# FPGA_GPIO.net
KiCad netlist of a schematic drawn in Altium Designer
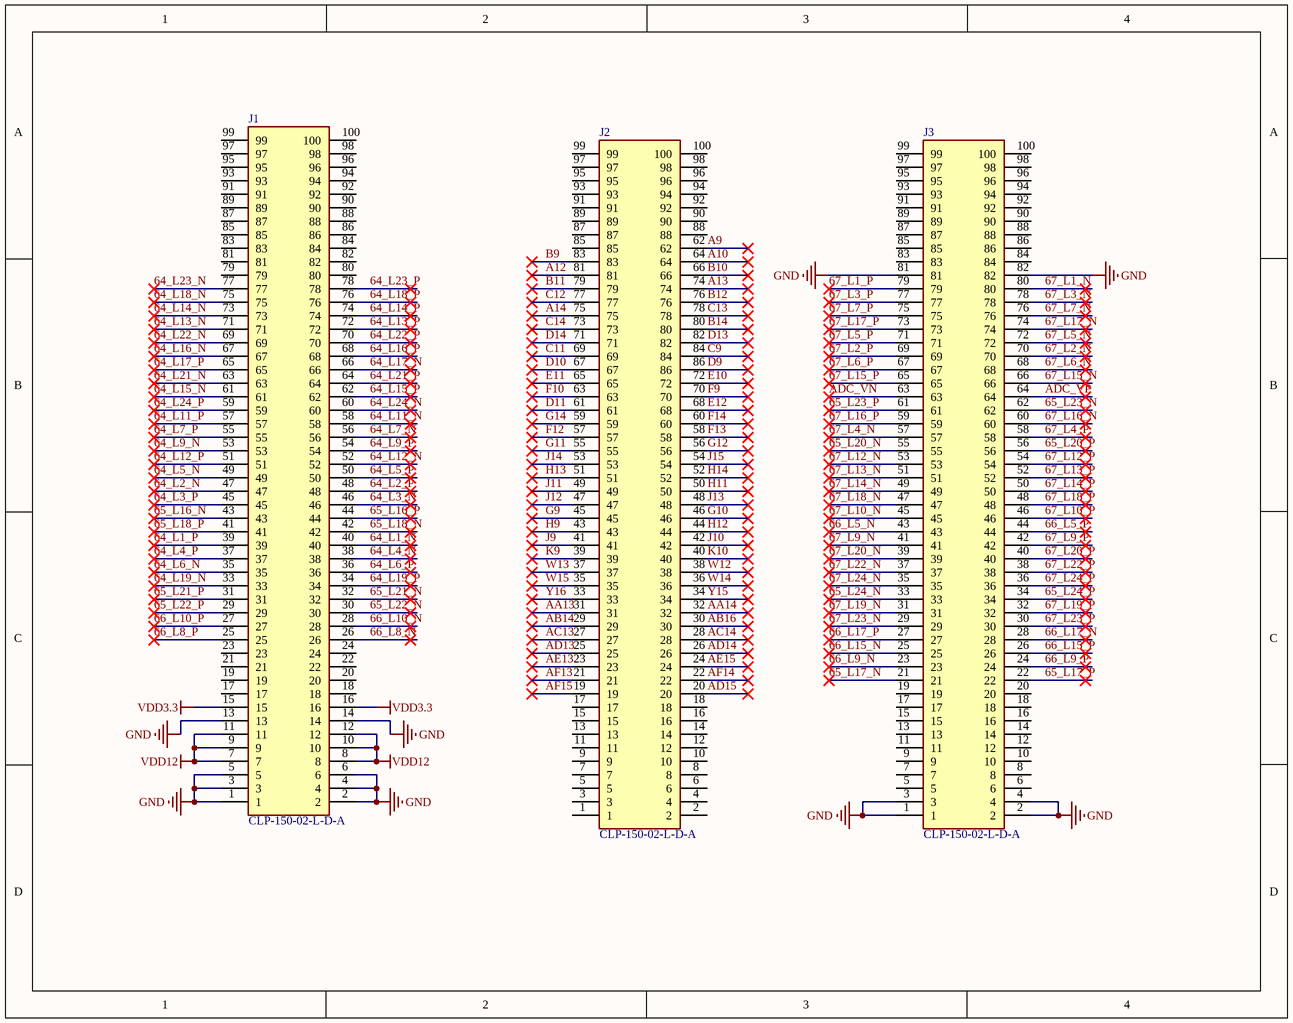
[diagram p0: FPGA_GPIO.SchDoc]

(export (version "E")
  (design (tool "Eeschema 10.0.6"))
  (components
    (comp (ref "J1")
      (value "CLP-150-02-L-D-A")
      (footprint "SamacSys:CLP-150-02-XXX-D-A")
      (description "Connector")
      (libsource (lib "") (part "CLP-150-02-L-D-A_1"))
    )
    (comp (ref "J2")
      (value "CLP-150-02-L-D-A")
      (footprint "SamacSys:CLP-150-02-XXX-D-A")
      (description "Connector")
      (libsource (lib "SamacSys") (part "CLP-150-02-L-D-A"))
    )
    (comp (ref "J3")
      (value "CLP-150-02-L-D-A")
      (footprint "SamacSys:CLP-150-02-XXX-D-A")
      (description "Connector")
      (libsource (lib "") (part "CLP-150-02-L-D-A_1"))
    )
  )
  (nets
    (net (code "1") (name "/64_L1_N") (class "Default")
      (node (ref "J1") (pin "40") (pinfunction "40_40") (pintype "passive"))
    )
    (net (code "2") (name "/64_L1_P") (class "Default")
      (node (ref "J1") (pin "39") (pinfunction "39_39") (pintype "passive+no_connect"))
    )
    (net (code "3") (name "/64_L2_N") (class "Default")
      (node (ref "J1") (pin "47") (pinfunction "47_47") (pintype "passive+no_connect"))
    )
    (net (code "4") (name "/64_L2_P") (class "Default")
      (node (ref "J1") (pin "48") (pinfunction "48_48") (pintype "passive"))
    )
    (net (code "5") (name "/64_L3_N") (class "Default")
      (node (ref "J1") (pin "46") (pinfunction "46_46") (pintype "passive"))
    )
    (net (code "6") (name "/64_L3_P") (class "Default")
      (node (ref "J1") (pin "45") (pinfunction "45_45") (pintype "passive+no_connect"))
    )
    (net (code "7") (name "/64_L4_N") (class "Default")
      (node (ref "J1") (pin "38") (pinfunction "38_38") (pintype "passive"))
    )
    (net (code "8") (name "/64_L4_P") (class "Default")
      (node (ref "J1") (pin "37") (pinfunction "37_37") (pintype "passive+no_connect"))
    )
    (net (code "9") (name "/64_L5_N") (class "Default")
      (node (ref "J1") (pin "49") (pinfunction "49_49") (pintype "passive+no_connect"))
    )
    (net (code "10") (name "/64_L5_P") (class "Default")
      (node (ref "J1") (pin "50") (pinfunction "50_50") (pintype "passive"))
    )
    (net (code "11") (name "/64_L6_N") (class "Default")
      (node (ref "J1") (pin "35") (pinfunction "35_35") (pintype "passive+no_connect"))
    )
    (net (code "12") (name "/64_L6_P") (class "Default")
      (node (ref "J1") (pin "36") (pinfunction "36_36") (pintype "passive"))
    )
    (net (code "13") (name "/64_L7_N") (class "Default")
      (node (ref "J1") (pin "56") (pinfunction "56_56") (pintype "passive"))
    )
    (net (code "14") (name "/64_L7_P") (class "Default")
      (node (ref "J1") (pin "55") (pinfunction "55_55") (pintype "passive+no_connect"))
    )
    (net (code "15") (name "/64_L9_N") (class "Default")
      (node (ref "J1") (pin "53") (pinfunction "53_53") (pintype "passive+no_connect"))
    )
    (net (code "16") (name "/64_L9_P") (class "Default")
      (node (ref "J1") (pin "54") (pinfunction "54_54") (pintype "passive"))
    )
    (net (code "17") (name "/64_L11_N") (class "Default")
      (node (ref "J1") (pin "58") (pinfunction "58_58") (pintype "passive"))
    )
    (net (code "18") (name "/64_L11_P") (class "Default")
      (node (ref "J1") (pin "57") (pinfunction "57_57") (pintype "passive+no_connect"))
    )
    (net (code "19") (name "/64_L12_N") (class "Default")
      (node (ref "J1") (pin "52") (pinfunction "52_52") (pintype "passive"))
    )
    (net (code "20") (name "/64_L12_P") (class "Default")
      (node (ref "J1") (pin "51") (pinfunction "51_51") (pintype "passive+no_connect"))
    )
    (net (code "21") (name "/64_L13_N") (class "Default")
      (node (ref "J1") (pin "71") (pinfunction "71_71") (pintype "passive+no_connect"))
    )
    (net (code "22") (name "/64_L13_P") (class "Default")
      (node (ref "J1") (pin "72") (pinfunction "72_72") (pintype "passive"))
    )
    (net (code "23") (name "/64_L14_N") (class "Default")
      (node (ref "J1") (pin "73") (pinfunction "73_73") (pintype "passive+no_connect"))
    )
    (net (code "24") (name "/64_L14_P") (class "Default")
      (node (ref "J1") (pin "74") (pinfunction "74_74") (pintype "passive"))
    )
    (net (code "25") (name "/64_L15_N") (class "Default")
      (node (ref "J1") (pin "61") (pinfunction "61_61") (pintype "passive+no_connect"))
    )
    (net (code "26") (name "/64_L15_P") (class "Default")
      (node (ref "J1") (pin "62") (pinfunction "62_62") (pintype "passive"))
    )
    (net (code "27") (name "/64_L16_N") (class "Default")
      (node (ref "J1") (pin "67") (pinfunction "67_67") (pintype "passive+no_connect"))
    )
    (net (code "28") (name "/64_L16_P") (class "Default")
      (node (ref "J1") (pin "68") (pinfunction "68_68") (pintype "passive"))
    )
    (net (code "29") (name "/64_L17_N") (class "Default")
      (node (ref "J1") (pin "66") (pinfunction "66_66") (pintype "passive"))
    )
    (net (code "30") (name "/64_L17_P") (class "Default")
      (node (ref "J1") (pin "65") (pinfunction "65_65") (pintype "passive+no_connect"))
    )
    (net (code "31") (name "/64_L18_N") (class "Default")
      (node (ref "J1") (pin "75") (pinfunction "75_75") (pintype "passive+no_connect"))
    )
    (net (code "32") (name "/64_L18_P") (class "Default")
      (node (ref "J1") (pin "76") (pinfunction "76_76") (pintype "passive"))
    )
    (net (code "33") (name "/64_L19_N") (class "Default")
      (node (ref "J1") (pin "33") (pinfunction "33_33") (pintype "passive+no_connect"))
    )
    (net (code "34") (name "/64_L19_P") (class "Default")
      (node (ref "J1") (pin "34") (pinfunction "34_34") (pintype "passive"))
    )
    (net (code "35") (name "/64_L21_N") (class "Default")
      (node (ref "J1") (pin "63") (pinfunction "63_63") (pintype "passive+no_connect"))
    )
    (net (code "36") (name "/64_L21_P") (class "Default")
      (node (ref "J1") (pin "64") (pinfunction "64_64") (pintype "passive"))
    )
    (net (code "37") (name "/64_L22_N") (class "Default")
      (node (ref "J1") (pin "69") (pinfunction "69_69") (pintype "passive+no_connect"))
    )
    (net (code "38") (name "/64_L22_P") (class "Default")
      (node (ref "J1") (pin "70") (pinfunction "70_70") (pintype "passive"))
    )
    (net (code "39") (name "/64_L23_N") (class "Default")
      (node (ref "J1") (pin "77") (pinfunction "77_77") (pintype "passive+no_connect"))
    )
    (net (code "40") (name "/64_L23_P") (class "Default")
      (node (ref "J1") (pin "78") (pinfunction "78_78") (pintype "passive"))
    )
    (net (code "41") (name "/64_L24_N") (class "Default")
      (node (ref "J1") (pin "60") (pinfunction "60_60") (pintype "passive"))
    )
    (net (code "42") (name "/64_L24_P") (class "Default")
      (node (ref "J1") (pin "59") (pinfunction "59_59") (pintype "passive+no_connect"))
    )
    (net (code "43") (name "/65_L16_N") (class "Default")
      (node (ref "J1") (pin "43") (pinfunction "43_43") (pintype "passive+no_connect"))
    )
    (net (code "44") (name "/65_L16_P") (class "Default")
      (node (ref "J1") (pin "44") (pinfunction "44_44") (pintype "passive"))
    )
    (net (code "45") (name "/65_L17_N") (class "Default")
      (node (ref "J3") (pin "21") (pinfunction "21_21") (pintype "passive+no_connect"))
    )
    (net (code "46") (name "/65_L17_P") (class "Default")
      (node (ref "J3") (pin "22") (pinfunction "22_22") (pintype "passive"))
    )
    (net (code "47") (name "/65_L18_N") (class "Default")
      (node (ref "J1") (pin "42") (pinfunction "42_42") (pintype "passive"))
    )
    (net (code "48") (name "/65_L18_P") (class "Default")
      (node (ref "J1") (pin "41") (pinfunction "41_41") (pintype "passive+no_connect"))
    )
    (net (code "49") (name "/65_L20_N") (class "Default")
      (node (ref "J3") (pin "55") (pinfunction "55_55") (pintype "passive+no_connect"))
    )
    (net (code "50") (name "/65_L20_P") (class "Default")
      (node (ref "J3") (pin "56") (pinfunction "56_56") (pintype "passive"))
    )
    (net (code "51") (name "/65_L21_N") (class "Default")
      (node (ref "J1") (pin "32") (pinfunction "32_32") (pintype "passive"))
    )
    (net (code "52") (name "/65_L21_P") (class "Default")
      (node (ref "J1") (pin "31") (pinfunction "31_31") (pintype "passive+no_connect"))
    )
    (net (code "53") (name "/65_L22_N") (class "Default")
      (node (ref "J1") (pin "30") (pinfunction "30_30") (pintype "passive"))
    )
    (net (code "54") (name "/65_L22_P") (class "Default")
      (node (ref "J1") (pin "29") (pinfunction "29_29") (pintype "passive+no_connect"))
    )
    (net (code "55") (name "/65_L23_N") (class "Default")
      (node (ref "J3") (pin "62") (pinfunction "62_62") (pintype "passive"))
    )
    (net (code "56") (name "/65_L23_P") (class "Default")
      (node (ref "J3") (pin "61") (pinfunction "61_61") (pintype "passive+no_connect"))
    )
    (net (code "57") (name "/65_L24_N") (class "Default")
      (node (ref "J3") (pin "33") (pinfunction "33_33") (pintype "passive+no_connect"))
    )
    (net (code "58") (name "/65_L24_P") (class "Default")
      (node (ref "J3") (pin "34") (pinfunction "34_34") (pintype "passive"))
    )
    (net (code "59") (name "/66_L5_N") (class "Default")
      (node (ref "J3") (pin "43") (pinfunction "43_43") (pintype "passive+no_connect"))
    )
    (net (code "60") (name "/66_L5_P") (class "Default")
      (node (ref "J3") (pin "44") (pinfunction "44_44") (pintype "passive"))
    )
    (net (code "61") (name "/66_L8_N") (class "Default")
      (node (ref "J1") (pin "26") (pinfunction "26_26") (pintype "passive"))
    )
    (net (code "62") (name "/66_L8_P") (class "Default")
      (node (ref "J1") (pin "25") (pinfunction "25_25") (pintype "passive+no_connect"))
    )
    (net (code "63") (name "/66_L9_N") (class "Default")
      (node (ref "J3") (pin "23") (pinfunction "23_23") (pintype "passive+no_connect"))
    )
    (net (code "64") (name "/66_L9_P") (class "Default")
      (node (ref "J3") (pin "24") (pinfunction "24_24") (pintype "passive"))
    )
    (net (code "65") (name "/66_L10_N") (class "Default")
      (node (ref "J1") (pin "28") (pinfunction "28_28") (pintype "passive"))
    )
    (net (code "66") (name "/66_L10_P") (class "Default")
      (node (ref "J1") (pin "27") (pinfunction "27_27") (pintype "passive+no_connect"))
    )
    (net (code "67") (name "/66_L15_N") (class "Default")
      (node (ref "J3") (pin "25") (pinfunction "25_25") (pintype "passive+no_connect"))
    )
    (net (code "68") (name "/66_L15_P") (class "Default")
      (node (ref "J3") (pin "26") (pinfunction "26_26") (pintype "passive"))
    )
    (net (code "69") (name "/66_L17_N") (class "Default")
      (node (ref "J3") (pin "28") (pinfunction "28_28") (pintype "passive"))
    )
    (net (code "70") (name "/66_L17_P") (class "Default")
      (node (ref "J3") (pin "27") (pinfunction "27_27") (pintype "passive+no_connect"))
    )
    (net (code "71") (name "/67_L1_N") (class "Default")
      (node (ref "J3") (pin "80") (pinfunction "80_80") (pintype "passive"))
    )
    (net (code "72") (name "/67_L1_P") (class "Default")
      (node (ref "J3") (pin "79") (pinfunction "79_79") (pintype "passive+no_connect"))
    )
    (net (code "73") (name "/67_L2_N") (class "Default")
      (node (ref "J3") (pin "70") (pinfunction "70_70") (pintype "passive"))
    )
    (net (code "74") (name "/67_L2_P") (class "Default")
      (node (ref "J3") (pin "69") (pinfunction "69_69") (pintype "passive+no_connect"))
    )
    (net (code "75") (name "/67_L3_N") (class "Default")
      (node (ref "J3") (pin "78") (pinfunction "78_78") (pintype "passive"))
    )
    (net (code "76") (name "/67_L3_P") (class "Default")
      (node (ref "J3") (pin "77") (pinfunction "77_77") (pintype "passive+no_connect"))
    )
    (net (code "77") (name "/67_L4_N") (class "Default")
      (node (ref "J3") (pin "57") (pinfunction "57_57") (pintype "passive+no_connect"))
    )
    (net (code "78") (name "/67_L4_P") (class "Default")
      (node (ref "J3") (pin "58") (pinfunction "58_58") (pintype "passive"))
    )
    (net (code "79") (name "/67_L5_N") (class "Default")
      (node (ref "J3") (pin "72") (pinfunction "72_72") (pintype "passive"))
    )
    (net (code "80") (name "/67_L5_P") (class "Default")
      (node (ref "J3") (pin "71") (pinfunction "71_71") (pintype "passive+no_connect"))
    )
    (net (code "81") (name "/67_L6_N") (class "Default")
      (node (ref "J3") (pin "68") (pinfunction "68_68") (pintype "passive"))
    )
    (net (code "82") (name "/67_L6_P") (class "Default")
      (node (ref "J3") (pin "67") (pinfunction "67_67") (pintype "passive+no_connect"))
    )
    (net (code "83") (name "/67_L7_N") (class "Default")
      (node (ref "J3") (pin "76") (pinfunction "76_76") (pintype "passive"))
    )
    (net (code "84") (name "/67_L7_P") (class "Default")
      (node (ref "J3") (pin "75") (pinfunction "75_75") (pintype "passive+no_connect"))
    )
    (net (code "85") (name "/67_L9_N") (class "Default")
      (node (ref "J3") (pin "41") (pinfunction "41_41") (pintype "passive+no_connect"))
    )
    (net (code "86") (name "/67_L9_P") (class "Default")
      (node (ref "J3") (pin "42") (pinfunction "42_42") (pintype "passive"))
    )
    (net (code "87") (name "/67_L10_N") (class "Default")
      (node (ref "J3") (pin "45") (pinfunction "45_45") (pintype "passive+no_connect"))
    )
    (net (code "88") (name "/67_L10_P") (class "Default")
      (node (ref "J3") (pin "46") (pinfunction "46_46") (pintype "passive"))
    )
    (net (code "89") (name "/67_L12_N") (class "Default")
      (node (ref "J3") (pin "53") (pinfunction "53_53") (pintype "passive+no_connect"))
    )
    (net (code "90") (name "/67_L12_P") (class "Default")
      (node (ref "J3") (pin "54") (pinfunction "54_54") (pintype "passive"))
    )
    (net (code "91") (name "/67_L13_N") (class "Default")
      (node (ref "J3") (pin "51") (pinfunction "51_51") (pintype "passive+no_connect"))
    )
    (net (code "92") (name "/67_L13_P") (class "Default")
      (node (ref "J3") (pin "52") (pinfunction "52_52") (pintype "passive"))
    )
    (net (code "93") (name "/67_L14_N") (class "Default")
      (node (ref "J3") (pin "49") (pinfunction "49_49") (pintype "passive+no_connect"))
    )
    (net (code "94") (name "/67_L14_P") (class "Default")
      (node (ref "J3") (pin "50") (pinfunction "50_50") (pintype "passive"))
    )
    (net (code "95") (name "/67_L15_N") (class "Default")
      (node (ref "J3") (pin "66") (pinfunction "66_66") (pintype "passive"))
    )
    (net (code "96") (name "/67_L15_P") (class "Default")
      (node (ref "J3") (pin "65") (pinfunction "65_65") (pintype "passive+no_connect"))
    )
    (net (code "97") (name "/67_L16_N") (class "Default")
      (node (ref "J3") (pin "60") (pinfunction "60_60") (pintype "passive"))
    )
    (net (code "98") (name "/67_L16_P") (class "Default")
      (node (ref "J3") (pin "59") (pinfunction "59_59") (pintype "passive+no_connect"))
    )
    (net (code "99") (name "/67_L17_N") (class "Default")
      (node (ref "J3") (pin "74") (pinfunction "74_74") (pintype "passive"))
    )
    (net (code "100") (name "/67_L17_P") (class "Default")
      (node (ref "J3") (pin "73") (pinfunction "73_73") (pintype "passive+no_connect"))
    )
    (net (code "101") (name "/67_L18_N") (class "Default")
      (node (ref "J3") (pin "47") (pinfunction "47_47") (pintype "passive+no_connect"))
    )
    (net (code "102") (name "/67_L18_P") (class "Default")
      (node (ref "J3") (pin "48") (pinfunction "48_48") (pintype "passive"))
    )
    (net (code "103") (name "/67_L19_N") (class "Default")
      (node (ref "J3") (pin "31") (pinfunction "31_31") (pintype "passive+no_connect"))
    )
    (net (code "104") (name "/67_L19_P") (class "Default")
      (node (ref "J3") (pin "32") (pinfunction "32_32") (pintype "passive"))
    )
    (net (code "105") (name "/67_L20_N") (class "Default")
      (node (ref "J3") (pin "39") (pinfunction "39_39") (pintype "passive+no_connect"))
    )
    (net (code "106") (name "/67_L20_P") (class "Default")
      (node (ref "J3") (pin "40") (pinfunction "40_40") (pintype "passive"))
    )
    (net (code "107") (name "/67_L22_N") (class "Default")
      (node (ref "J3") (pin "37") (pinfunction "37_37") (pintype "passive+no_connect"))
    )
    (net (code "108") (name "/67_L22_P") (class "Default")
      (node (ref "J3") (pin "38") (pinfunction "38_38") (pintype "passive"))
    )
    (net (code "109") (name "/67_L23_N") (class "Default")
      (node (ref "J3") (pin "29") (pinfunction "29_29") (pintype "passive+no_connect"))
    )
    (net (code "110") (name "/67_L23_P") (class "Default")
      (node (ref "J3") (pin "30") (pinfunction "30_30") (pintype "passive"))
    )
    (net (code "111") (name "/67_L24_N") (class "Default")
      (node (ref "J3") (pin "35") (pinfunction "35_35") (pintype "passive+no_connect"))
    )
    (net (code "112") (name "/67_L24_P") (class "Default")
      (node (ref "J3") (pin "36") (pinfunction "36_36") (pintype "passive"))
    )
    (net (code "113") (name "/A9") (class "Default")
      (node (ref "J2") (pin "62") (pinfunction "62_62") (pintype "passive+no_connect"))
    )
    (net (code "114") (name "/A10") (class "Default")
      (node (ref "J2") (pin "64") (pinfunction "64_64") (pintype "passive+no_connect"))
    )
    (net (code "115") (name "/A12") (class "Default")
      (node (ref "J2") (pin "81") (pinfunction "81_81") (pintype "passive+no_connect"))
    )
    (net (code "116") (name "/A13") (class "Default")
      (node (ref "J2") (pin "74") (pinfunction "74_74") (pintype "passive+no_connect"))
    )
    (net (code "117") (name "/A14") (class "Default")
      (node (ref "J2") (pin "75") (pinfunction "75_75") (pintype "passive+no_connect"))
    )
    (net (code "118") (name "/AA13") (class "Default")
      (node (ref "J2") (pin "31") (pinfunction "31_31") (pintype "passive+no_connect"))
    )
    (net (code "119") (name "/AA14") (class "Default")
      (node (ref "J2") (pin "32") (pinfunction "32_32") (pintype "passive+no_connect"))
    )
    (net (code "120") (name "/AB14") (class "Default")
      (node (ref "J2") (pin "29") (pinfunction "29_29") (pintype "passive+no_connect"))
    )
    (net (code "121") (name "/AB16") (class "Default")
      (node (ref "J2") (pin "30") (pinfunction "30_30") (pintype "passive+no_connect"))
    )
    (net (code "122") (name "/AC13") (class "Default")
      (node (ref "J2") (pin "27") (pinfunction "27_27") (pintype "passive+no_connect"))
    )
    (net (code "123") (name "/AC14") (class "Default")
      (node (ref "J2") (pin "28") (pinfunction "28_28") (pintype "passive+no_connect"))
    )
    (net (code "124") (name "/AD13") (class "Default")
      (node (ref "J2") (pin "25") (pinfunction "25_25") (pintype "passive+no_connect"))
    )
    (net (code "125") (name "/AD14") (class "Default")
      (node (ref "J2") (pin "26") (pinfunction "26_26") (pintype "passive+no_connect"))
    )
    (net (code "126") (name "/AD15") (class "Default")
      (node (ref "J2") (pin "20") (pinfunction "20_20") (pintype "passive+no_connect"))
    )
    (net (code "127") (name "/ADC_VN") (class "Default")
      (node (ref "J3") (pin "63") (pinfunction "63_63") (pintype "passive+no_connect"))
    )
    (net (code "128") (name "/ADC_VP") (class "Default")
      (node (ref "J3") (pin "64") (pinfunction "64_64") (pintype "passive"))
    )
    (net (code "129") (name "/AE13") (class "Default")
      (node (ref "J2") (pin "23") (pinfunction "23_23") (pintype "passive+no_connect"))
    )
    (net (code "130") (name "/AE15") (class "Default")
      (node (ref "J2") (pin "24") (pinfunction "24_24") (pintype "passive+no_connect"))
    )
    (net (code "131") (name "/AF13") (class "Default")
      (node (ref "J2") (pin "21") (pinfunction "21_21") (pintype "passive+no_connect"))
    )
    (net (code "132") (name "/AF14") (class "Default")
      (node (ref "J2") (pin "22") (pinfunction "22_22") (pintype "passive+no_connect"))
    )
    (net (code "133") (name "/AF15") (class "Default")
      (node (ref "J2") (pin "19") (pinfunction "19_19") (pintype "passive+no_connect"))
    )
    (net (code "134") (name "/B9") (class "Default")
      (node (ref "J2") (pin "83") (pinfunction "83_83") (pintype "passive+no_connect"))
    )
    (net (code "135") (name "/B10") (class "Default")
      (node (ref "J2") (pin "66") (pinfunction "66_66") (pintype "passive+no_connect"))
    )
    (net (code "136") (name "/B11") (class "Default")
      (node (ref "J2") (pin "79") (pinfunction "79_79") (pintype "passive+no_connect"))
    )
    (net (code "137") (name "/B12") (class "Default")
      (node (ref "J2") (pin "76") (pinfunction "76_76") (pintype "passive+no_connect"))
    )
    (net (code "138") (name "/B14") (class "Default")
      (node (ref "J2") (pin "80") (pinfunction "80_80") (pintype "passive+no_connect"))
    )
    (net (code "139") (name "/C9") (class "Default")
      (node (ref "J2") (pin "84") (pinfunction "84_84") (pintype "passive+no_connect"))
    )
    (net (code "140") (name "/C11") (class "Default")
      (node (ref "J2") (pin "69") (pinfunction "69_69") (pintype "passive+no_connect"))
    )
    (net (code "141") (name "/C12") (class "Default")
      (node (ref "J2") (pin "77") (pinfunction "77_77") (pintype "passive+no_connect"))
    )
    (net (code "142") (name "/C13") (class "Default")
      (node (ref "J2") (pin "78") (pinfunction "78_78") (pintype "passive+no_connect"))
    )
    (net (code "143") (name "/C14") (class "Default")
      (node (ref "J2") (pin "73") (pinfunction "73_73") (pintype "passive+no_connect"))
    )
    (net (code "144") (name "/D9") (class "Default")
      (node (ref "J2") (pin "86") (pinfunction "86_86") (pintype "passive+no_connect"))
    )
    (net (code "145") (name "/D10") (class "Default")
      (node (ref "J2") (pin "67") (pinfunction "67_67") (pintype "passive+no_connect"))
    )
    (net (code "146") (name "/D11") (class "Default")
      (node (ref "J2") (pin "61") (pinfunction "61_61") (pintype "passive+no_connect"))
    )
    (net (code "147") (name "/D13") (class "Default")
      (node (ref "J2") (pin "82") (pinfunction "82_82") (pintype "passive+no_connect"))
    )
    (net (code "148") (name "/D14") (class "Default")
      (node (ref "J2") (pin "71") (pinfunction "71_71") (pintype "passive+no_connect"))
    )
    (net (code "149") (name "/E10") (class "Default")
      (node (ref "J2") (pin "72") (pinfunction "72_72") (pintype "passive+no_connect"))
    )
    (net (code "150") (name "/E11") (class "Default")
      (node (ref "J2") (pin "65") (pinfunction "65_65") (pintype "passive+no_connect"))
    )
    (net (code "151") (name "/E12") (class "Default")
      (node (ref "J2") (pin "68") (pinfunction "68_68") (pintype "passive+no_connect"))
    )
    (net (code "152") (name "/F9") (class "Default")
      (node (ref "J2") (pin "70") (pinfunction "70_70") (pintype "passive+no_connect"))
    )
    (net (code "153") (name "/F10") (class "Default")
      (node (ref "J2") (pin "63") (pinfunction "63_63") (pintype "passive+no_connect"))
    )
    (net (code "154") (name "/F12") (class "Default")
      (node (ref "J2") (pin "57") (pinfunction "57_57") (pintype "passive+no_connect"))
    )
    (net (code "155") (name "/F13") (class "Default")
      (node (ref "J2") (pin "58") (pinfunction "58_58") (pintype "passive+no_connect"))
    )
    (net (code "156") (name "/F14") (class "Default")
      (node (ref "J2") (pin "60") (pinfunction "60_60") (pintype "passive+no_connect"))
    )
    (net (code "157") (name "/G9") (class "Default")
      (node (ref "J2") (pin "45") (pinfunction "45_45") (pintype "passive+no_connect"))
    )
    (net (code "158") (name "/G10") (class "Default")
      (node (ref "J2") (pin "46") (pinfunction "46_46") (pintype "passive+no_connect"))
    )
    (net (code "159") (name "/G11") (class "Default")
      (node (ref "J2") (pin "55") (pinfunction "55_55") (pintype "passive+no_connect"))
    )
    (net (code "160") (name "/G12") (class "Default")
      (node (ref "J2") (pin "56") (pinfunction "56_56") (pintype "passive+no_connect"))
    )
    (net (code "161") (name "/G14") (class "Default")
      (node (ref "J2") (pin "59") (pinfunction "59_59") (pintype "passive+no_connect"))
    )
    (net (code "162") (name "/H9") (class "Default")
      (node (ref "J2") (pin "43") (pinfunction "43_43") (pintype "passive+no_connect"))
    )
    (net (code "163") (name "/H11") (class "Default")
      (node (ref "J2") (pin "50") (pinfunction "50_50") (pintype "passive+no_connect"))
    )
    (net (code "164") (name "/H12") (class "Default")
      (node (ref "J2") (pin "44") (pinfunction "44_44") (pintype "passive+no_connect"))
    )
    (net (code "165") (name "/H13") (class "Default")
      (node (ref "J2") (pin "51") (pinfunction "51_51") (pintype "passive+no_connect"))
    )
    (net (code "166") (name "/H14") (class "Default")
      (node (ref "J2") (pin "52") (pinfunction "52_52") (pintype "passive+no_connect"))
    )
    (net (code "167") (name "/J9") (class "Default")
      (node (ref "J2") (pin "41") (pinfunction "41_41") (pintype "passive+no_connect"))
    )
    (net (code "168") (name "/J10") (class "Default")
      (node (ref "J2") (pin "42") (pinfunction "42_42") (pintype "passive+no_connect"))
    )
    (net (code "169") (name "/J11") (class "Default")
      (node (ref "J2") (pin "49") (pinfunction "49_49") (pintype "passive+no_connect"))
    )
    (net (code "170") (name "/J12") (class "Default")
      (node (ref "J2") (pin "47") (pinfunction "47_47") (pintype "passive+no_connect"))
    )
    (net (code "171") (name "/J13") (class "Default")
      (node (ref "J2") (pin "48") (pinfunction "48_48") (pintype "passive+no_connect"))
    )
    (net (code "172") (name "/J14") (class "Default")
      (node (ref "J2") (pin "53") (pinfunction "53_53") (pintype "passive+no_connect"))
    )
    (net (code "173") (name "/J15") (class "Default")
      (node (ref "J2") (pin "54") (pinfunction "54_54") (pintype "passive+no_connect"))
    )
    (net (code "174") (name "/K9") (class "Default")
      (node (ref "J2") (pin "39") (pinfunction "39_39") (pintype "passive+no_connect"))
    )
    (net (code "175") (name "/K10") (class "Default")
      (node (ref "J2") (pin "40") (pinfunction "40_40") (pintype "passive+no_connect"))
    )
    (net (code "176") (name "/W12") (class "Default")
      (node (ref "J2") (pin "38") (pinfunction "38_38") (pintype "passive+no_connect"))
    )
    (net (code "177") (name "/W13") (class "Default")
      (node (ref "J2") (pin "37") (pinfunction "37_37") (pintype "passive+no_connect"))
    )
    (net (code "178") (name "/W14") (class "Default")
      (node (ref "J2") (pin "36") (pinfunction "36_36") (pintype "passive+no_connect"))
    )
    (net (code "179") (name "/W15") (class "Default")
      (node (ref "J2") (pin "35") (pinfunction "35_35") (pintype "passive+no_connect"))
    )
    (net (code "180") (name "/Y15") (class "Default")
      (node (ref "J2") (pin "34") (pinfunction "34_34") (pintype "passive+no_connect"))
    )
    (net (code "181") (name "/Y16") (class "Default")
      (node (ref "J2") (pin "33") (pinfunction "33_33") (pintype "passive+no_connect"))
    )
    (net (code "182") (name "GND") (class "Default")
      (node (ref "J1") (pin "1") (pinfunction "1_1") (pintype "passive"))
      (node (ref "J1") (pin "13") (pinfunction "13_13") (pintype "passive"))
      (node (ref "J1") (pin "14") (pinfunction "14_14") (pintype "passive"))
      (node (ref "J1") (pin "2") (pinfunction "2_2") (pintype "passive"))
      (node (ref "J1") (pin "3") (pinfunction "3_3") (pintype "passive"))
      (node (ref "J1") (pin "4") (pinfunction "4_4") (pintype "passive"))
      (node (ref "J1") (pin "5") (pinfunction "5_5") (pintype "passive"))
      (node (ref "J1") (pin "6") (pinfunction "6_6") (pintype "passive"))
      (node (ref "J3") (pin "1") (pinfunction "1_1") (pintype "passive"))
      (node (ref "J3") (pin "2") (pinfunction "2_2") (pintype "passive"))
      (node (ref "J3") (pin "3") (pinfunction "3_3") (pintype "passive"))
      (node (ref "J3") (pin "4") (pinfunction "4_4") (pintype "passive"))
      (node (ref "J3") (pin "81") (pinfunction "81_81") (pintype "passive"))
      (node (ref "J3") (pin "82") (pinfunction "82_82") (pintype "passive"))
    )
    (net (code "183") (name "VDD3.3") (class "Default")
      (node (ref "J1") (pin "15") (pinfunction "15_15") (pintype "passive"))
      (node (ref "J1") (pin "16") (pinfunction "16_16") (pintype "passive"))
    )
    (net (code "184") (name "VDD12") (class "Default")
      (node (ref "J1") (pin "10") (pinfunction "10_10") (pintype "passive"))
      (node (ref "J1") (pin "11") (pinfunction "11_11") (pintype "passive"))
      (node (ref "J1") (pin "12") (pinfunction "12_12") (pintype "passive"))
      (node (ref "J1") (pin "7") (pinfunction "7_7") (pintype "passive"))
      (node (ref "J1") (pin "8") (pinfunction "8_8") (pintype "passive"))
      (node (ref "J1") (pin "9") (pinfunction "9_9") (pintype "passive"))
    )
    (net (code "185") (name "unconnected-(J1-Pad17)") (class "Default")
      (node (ref "J1") (pin "17") (pinfunction "17_17") (pintype "passive"))
    )
    (net (code "186") (name "unconnected-(J1-Pad18)") (class "Default")
      (node (ref "J1") (pin "18") (pinfunction "18_18") (pintype "passive"))
    )
    (net (code "187") (name "unconnected-(J1-Pad19)") (class "Default")
      (node (ref "J1") (pin "19") (pinfunction "19_19") (pintype "passive"))
    )
    (net (code "188") (name "unconnected-(J1-Pad20)") (class "Default")
      (node (ref "J1") (pin "20") (pinfunction "20_20") (pintype "passive"))
    )
    (net (code "189") (name "unconnected-(J1-Pad21)") (class "Default")
      (node (ref "J1") (pin "21") (pinfunction "21_21") (pintype "passive"))
    )
    (net (code "190") (name "unconnected-(J1-Pad22)") (class "Default")
      (node (ref "J1") (pin "22") (pinfunction "22_22") (pintype "passive"))
    )
    (net (code "191") (name "unconnected-(J1-Pad23)") (class "Default")
      (node (ref "J1") (pin "23") (pinfunction "23_23") (pintype "passive"))
    )
    (net (code "192") (name "unconnected-(J1-Pad24)") (class "Default")
      (node (ref "J1") (pin "24") (pinfunction "24_24") (pintype "passive"))
    )
    (net (code "193") (name "unconnected-(J1-Pad79)") (class "Default")
      (node (ref "J1") (pin "79") (pinfunction "79_79") (pintype "passive"))
    )
    (net (code "194") (name "unconnected-(J1-Pad80)") (class "Default")
      (node (ref "J1") (pin "80") (pinfunction "80_80") (pintype "passive"))
    )
    (net (code "195") (name "unconnected-(J1-Pad81)") (class "Default")
      (node (ref "J1") (pin "81") (pinfunction "81_81") (pintype "passive"))
    )
    (net (code "196") (name "unconnected-(J1-Pad82)") (class "Default")
      (node (ref "J1") (pin "82") (pinfunction "82_82") (pintype "passive"))
    )
    (net (code "197") (name "unconnected-(J1-Pad83)") (class "Default")
      (node (ref "J1") (pin "83") (pinfunction "83_83") (pintype "passive"))
    )
    (net (code "198") (name "unconnected-(J1-Pad84)") (class "Default")
      (node (ref "J1") (pin "84") (pinfunction "84_84") (pintype "passive"))
    )
    (net (code "199") (name "unconnected-(J1-Pad85)") (class "Default")
      (node (ref "J1") (pin "85") (pinfunction "85_85") (pintype "passive"))
    )
    (net (code "200") (name "unconnected-(J1-Pad86)") (class "Default")
      (node (ref "J1") (pin "86") (pinfunction "86_86") (pintype "passive"))
    )
    (net (code "201") (name "unconnected-(J1-Pad87)") (class "Default")
      (node (ref "J1") (pin "87") (pinfunction "87_87") (pintype "passive"))
    )
    (net (code "202") (name "unconnected-(J1-Pad88)") (class "Default")
      (node (ref "J1") (pin "88") (pinfunction "88_88") (pintype "passive"))
    )
    (net (code "203") (name "unconnected-(J1-Pad89)") (class "Default")
      (node (ref "J1") (pin "89") (pinfunction "89_89") (pintype "passive"))
    )
    (net (code "204") (name "unconnected-(J1-Pad90)") (class "Default")
      (node (ref "J1") (pin "90") (pinfunction "90_90") (pintype "passive"))
    )
    (net (code "205") (name "unconnected-(J1-Pad91)") (class "Default")
      (node (ref "J1") (pin "91") (pinfunction "91_91") (pintype "passive"))
    )
    (net (code "206") (name "unconnected-(J1-Pad92)") (class "Default")
      (node (ref "J1") (pin "92") (pinfunction "92_92") (pintype "passive"))
    )
    (net (code "207") (name "unconnected-(J1-Pad93)") (class "Default")
      (node (ref "J1") (pin "93") (pinfunction "93_93") (pintype "passive"))
    )
    (net (code "208") (name "unconnected-(J1-Pad94)") (class "Default")
      (node (ref "J1") (pin "94") (pinfunction "94_94") (pintype "passive"))
    )
    (net (code "209") (name "unconnected-(J1-Pad95)") (class "Default")
      (node (ref "J1") (pin "95") (pinfunction "95_95") (pintype "passive"))
    )
    (net (code "210") (name "unconnected-(J1-Pad96)") (class "Default")
      (node (ref "J1") (pin "96") (pinfunction "96_96") (pintype "passive"))
    )
    (net (code "211") (name "unconnected-(J1-Pad97)") (class "Default")
      (node (ref "J1") (pin "97") (pinfunction "97_97") (pintype "passive"))
    )
    (net (code "212") (name "unconnected-(J1-Pad98)") (class "Default")
      (node (ref "J1") (pin "98") (pinfunction "98_98") (pintype "passive"))
    )
    (net (code "213") (name "unconnected-(J1-Pad99)") (class "Default")
      (node (ref "J1") (pin "99") (pinfunction "99_99") (pintype "passive"))
    )
    (net (code "214") (name "unconnected-(J1-Pad100)") (class "Default")
      (node (ref "J1") (pin "100") (pinfunction "100_100") (pintype "passive"))
    )
    (net (code "215") (name "unconnected-(J2-Pad1)") (class "Default")
      (node (ref "J2") (pin "1") (pinfunction "1_1") (pintype "passive"))
    )
    (net (code "216") (name "unconnected-(J2-Pad2)") (class "Default")
      (node (ref "J2") (pin "2") (pinfunction "2_2") (pintype "passive"))
    )
    (net (code "217") (name "unconnected-(J2-Pad3)") (class "Default")
      (node (ref "J2") (pin "3") (pinfunction "3_3") (pintype "passive"))
    )
    (net (code "218") (name "unconnected-(J2-Pad4)") (class "Default")
      (node (ref "J2") (pin "4") (pinfunction "4_4") (pintype "passive"))
    )
    (net (code "219") (name "unconnected-(J2-Pad5)") (class "Default")
      (node (ref "J2") (pin "5") (pinfunction "5_5") (pintype "passive"))
    )
    (net (code "220") (name "unconnected-(J2-Pad6)") (class "Default")
      (node (ref "J2") (pin "6") (pinfunction "6_6") (pintype "passive"))
    )
    (net (code "221") (name "unconnected-(J2-Pad7)") (class "Default")
      (node (ref "J2") (pin "7") (pinfunction "7_7") (pintype "passive"))
    )
    (net (code "222") (name "unconnected-(J2-Pad8)") (class "Default")
      (node (ref "J2") (pin "8") (pinfunction "8_8") (pintype "passive"))
    )
    (net (code "223") (name "unconnected-(J2-Pad9)") (class "Default")
      (node (ref "J2") (pin "9") (pinfunction "9_9") (pintype "passive"))
    )
    (net (code "224") (name "unconnected-(J2-Pad10)") (class "Default")
      (node (ref "J2") (pin "10") (pinfunction "10_10") (pintype "passive"))
    )
    (net (code "225") (name "unconnected-(J2-Pad11)") (class "Default")
      (node (ref "J2") (pin "11") (pinfunction "11_11") (pintype "passive"))
    )
    (net (code "226") (name "unconnected-(J2-Pad12)") (class "Default")
      (node (ref "J2") (pin "12") (pinfunction "12_12") (pintype "passive"))
    )
    (net (code "227") (name "unconnected-(J2-Pad13)") (class "Default")
      (node (ref "J2") (pin "13") (pinfunction "13_13") (pintype "passive"))
    )
    (net (code "228") (name "unconnected-(J2-Pad14)") (class "Default")
      (node (ref "J2") (pin "14") (pinfunction "14_14") (pintype "passive"))
    )
    (net (code "229") (name "unconnected-(J2-Pad15)") (class "Default")
      (node (ref "J2") (pin "15") (pinfunction "15_15") (pintype "passive"))
    )
    (net (code "230") (name "unconnected-(J2-Pad16)") (class "Default")
      (node (ref "J2") (pin "16") (pinfunction "16_16") (pintype "passive"))
    )
    (net (code "231") (name "unconnected-(J2-Pad17)") (class "Default")
      (node (ref "J2") (pin "17") (pinfunction "17_17") (pintype "passive"))
    )
    (net (code "232") (name "unconnected-(J2-Pad18)") (class "Default")
      (node (ref "J2") (pin "18") (pinfunction "18_18") (pintype "passive"))
    )
    (net (code "233") (name "unconnected-(J2-Pad85)") (class "Default")
      (node (ref "J2") (pin "85") (pinfunction "85_85") (pintype "passive"))
    )
    (net (code "234") (name "unconnected-(J2-Pad87)") (class "Default")
      (node (ref "J2") (pin "87") (pinfunction "87_87") (pintype "passive"))
    )
    (net (code "235") (name "unconnected-(J2-Pad88)") (class "Default")
      (node (ref "J2") (pin "88") (pinfunction "88_88") (pintype "passive"))
    )
    (net (code "236") (name "unconnected-(J2-Pad89)") (class "Default")
      (node (ref "J2") (pin "89") (pinfunction "89_89") (pintype "passive"))
    )
    (net (code "237") (name "unconnected-(J2-Pad90)") (class "Default")
      (node (ref "J2") (pin "90") (pinfunction "90_90") (pintype "passive"))
    )
    (net (code "238") (name "unconnected-(J2-Pad91)") (class "Default")
      (node (ref "J2") (pin "91") (pinfunction "91_91") (pintype "passive"))
    )
    (net (code "239") (name "unconnected-(J2-Pad92)") (class "Default")
      (node (ref "J2") (pin "92") (pinfunction "92_92") (pintype "passive"))
    )
    (net (code "240") (name "unconnected-(J2-Pad93)") (class "Default")
      (node (ref "J2") (pin "93") (pinfunction "93_93") (pintype "passive"))
    )
    (net (code "241") (name "unconnected-(J2-Pad94)") (class "Default")
      (node (ref "J2") (pin "94") (pinfunction "94_94") (pintype "passive"))
    )
    (net (code "242") (name "unconnected-(J2-Pad95)") (class "Default")
      (node (ref "J2") (pin "95") (pinfunction "95_95") (pintype "passive"))
    )
    (net (code "243") (name "unconnected-(J2-Pad96)") (class "Default")
      (node (ref "J2") (pin "96") (pinfunction "96_96") (pintype "passive"))
    )
    (net (code "244") (name "unconnected-(J2-Pad97)") (class "Default")
      (node (ref "J2") (pin "97") (pinfunction "97_97") (pintype "passive"))
    )
    (net (code "245") (name "unconnected-(J2-Pad98)") (class "Default")
      (node (ref "J2") (pin "98") (pinfunction "98_98") (pintype "passive"))
    )
    (net (code "246") (name "unconnected-(J2-Pad99)") (class "Default")
      (node (ref "J2") (pin "99") (pinfunction "99_99") (pintype "passive"))
    )
    (net (code "247") (name "unconnected-(J2-Pad100)") (class "Default")
      (node (ref "J2") (pin "100") (pinfunction "100_100") (pintype "passive"))
    )
    (net (code "248") (name "unconnected-(J3-Pad5)") (class "Default")
      (node (ref "J3") (pin "5") (pinfunction "5_5") (pintype "passive"))
    )
    (net (code "249") (name "unconnected-(J3-Pad6)") (class "Default")
      (node (ref "J3") (pin "6") (pinfunction "6_6") (pintype "passive"))
    )
    (net (code "250") (name "unconnected-(J3-Pad7)") (class "Default")
      (node (ref "J3") (pin "7") (pinfunction "7_7") (pintype "passive"))
    )
    (net (code "251") (name "unconnected-(J3-Pad8)") (class "Default")
      (node (ref "J3") (pin "8") (pinfunction "8_8") (pintype "passive"))
    )
    (net (code "252") (name "unconnected-(J3-Pad9)") (class "Default")
      (node (ref "J3") (pin "9") (pinfunction "9_9") (pintype "passive"))
    )
    (net (code "253") (name "unconnected-(J3-Pad10)") (class "Default")
      (node (ref "J3") (pin "10") (pinfunction "10_10") (pintype "passive"))
    )
    (net (code "254") (name "unconnected-(J3-Pad11)") (class "Default")
      (node (ref "J3") (pin "11") (pinfunction "11_11") (pintype "passive"))
    )
    (net (code "255") (name "unconnected-(J3-Pad12)") (class "Default")
      (node (ref "J3") (pin "12") (pinfunction "12_12") (pintype "passive"))
    )
    (net (code "256") (name "unconnected-(J3-Pad13)") (class "Default")
      (node (ref "J3") (pin "13") (pinfunction "13_13") (pintype "passive"))
    )
    (net (code "257") (name "unconnected-(J3-Pad14)") (class "Default")
      (node (ref "J3") (pin "14") (pinfunction "14_14") (pintype "passive"))
    )
    (net (code "258") (name "unconnected-(J3-Pad15)") (class "Default")
      (node (ref "J3") (pin "15") (pinfunction "15_15") (pintype "passive"))
    )
    (net (code "259") (name "unconnected-(J3-Pad16)") (class "Default")
      (node (ref "J3") (pin "16") (pinfunction "16_16") (pintype "passive"))
    )
    (net (code "260") (name "unconnected-(J3-Pad17)") (class "Default")
      (node (ref "J3") (pin "17") (pinfunction "17_17") (pintype "passive"))
    )
    (net (code "261") (name "unconnected-(J3-Pad18)") (class "Default")
      (node (ref "J3") (pin "18") (pinfunction "18_18") (pintype "passive"))
    )
    (net (code "262") (name "unconnected-(J3-Pad19)") (class "Default")
      (node (ref "J3") (pin "19") (pinfunction "19_19") (pintype "passive"))
    )
    (net (code "263") (name "unconnected-(J3-Pad20)") (class "Default")
      (node (ref "J3") (pin "20") (pinfunction "20_20") (pintype "passive"))
    )
    (net (code "264") (name "unconnected-(J3-Pad83)") (class "Default")
      (node (ref "J3") (pin "83") (pinfunction "83_83") (pintype "passive"))
    )
    (net (code "265") (name "unconnected-(J3-Pad84)") (class "Default")
      (node (ref "J3") (pin "84") (pinfunction "84_84") (pintype "passive"))
    )
    (net (code "266") (name "unconnected-(J3-Pad85)") (class "Default")
      (node (ref "J3") (pin "85") (pinfunction "85_85") (pintype "passive"))
    )
    (net (code "267") (name "unconnected-(J3-Pad86)") (class "Default")
      (node (ref "J3") (pin "86") (pinfunction "86_86") (pintype "passive"))
    )
    (net (code "268") (name "unconnected-(J3-Pad87)") (class "Default")
      (node (ref "J3") (pin "87") (pinfunction "87_87") (pintype "passive"))
    )
    (net (code "269") (name "unconnected-(J3-Pad88)") (class "Default")
      (node (ref "J3") (pin "88") (pinfunction "88_88") (pintype "passive"))
    )
    (net (code "270") (name "unconnected-(J3-Pad89)") (class "Default")
      (node (ref "J3") (pin "89") (pinfunction "89_89") (pintype "passive"))
    )
    (net (code "271") (name "unconnected-(J3-Pad90)") (class "Default")
      (node (ref "J3") (pin "90") (pinfunction "90_90") (pintype "passive"))
    )
    (net (code "272") (name "unconnected-(J3-Pad91)") (class "Default")
      (node (ref "J3") (pin "91") (pinfunction "91_91") (pintype "passive"))
    )
    (net (code "273") (name "unconnected-(J3-Pad92)") (class "Default")
      (node (ref "J3") (pin "92") (pinfunction "92_92") (pintype "passive"))
    )
    (net (code "274") (name "unconnected-(J3-Pad93)") (class "Default")
      (node (ref "J3") (pin "93") (pinfunction "93_93") (pintype "passive"))
    )
    (net (code "275") (name "unconnected-(J3-Pad94)") (class "Default")
      (node (ref "J3") (pin "94") (pinfunction "94_94") (pintype "passive"))
    )
    (net (code "276") (name "unconnected-(J3-Pad95)") (class "Default")
      (node (ref "J3") (pin "95") (pinfunction "95_95") (pintype "passive"))
    )
    (net (code "277") (name "unconnected-(J3-Pad96)") (class "Default")
      (node (ref "J3") (pin "96") (pinfunction "96_96") (pintype "passive"))
    )
    (net (code "278") (name "unconnected-(J3-Pad97)") (class "Default")
      (node (ref "J3") (pin "97") (pinfunction "97_97") (pintype "passive"))
    )
    (net (code "279") (name "unconnected-(J3-Pad98)") (class "Default")
      (node (ref "J3") (pin "98") (pinfunction "98_98") (pintype "passive"))
    )
    (net (code "280") (name "unconnected-(J3-Pad99)") (class "Default")
      (node (ref "J3") (pin "99") (pinfunction "99_99") (pintype "passive"))
    )
    (net (code "281") (name "unconnected-(J3-Pad100)") (class "Default")
      (node (ref "J3") (pin "100") (pinfunction "100_100") (pintype "passive"))
    )
  )
)
